# PCI_short_card_universal_-_32_BIT-6.net
KiCad netlist of a schematic drawn in Altium Designer
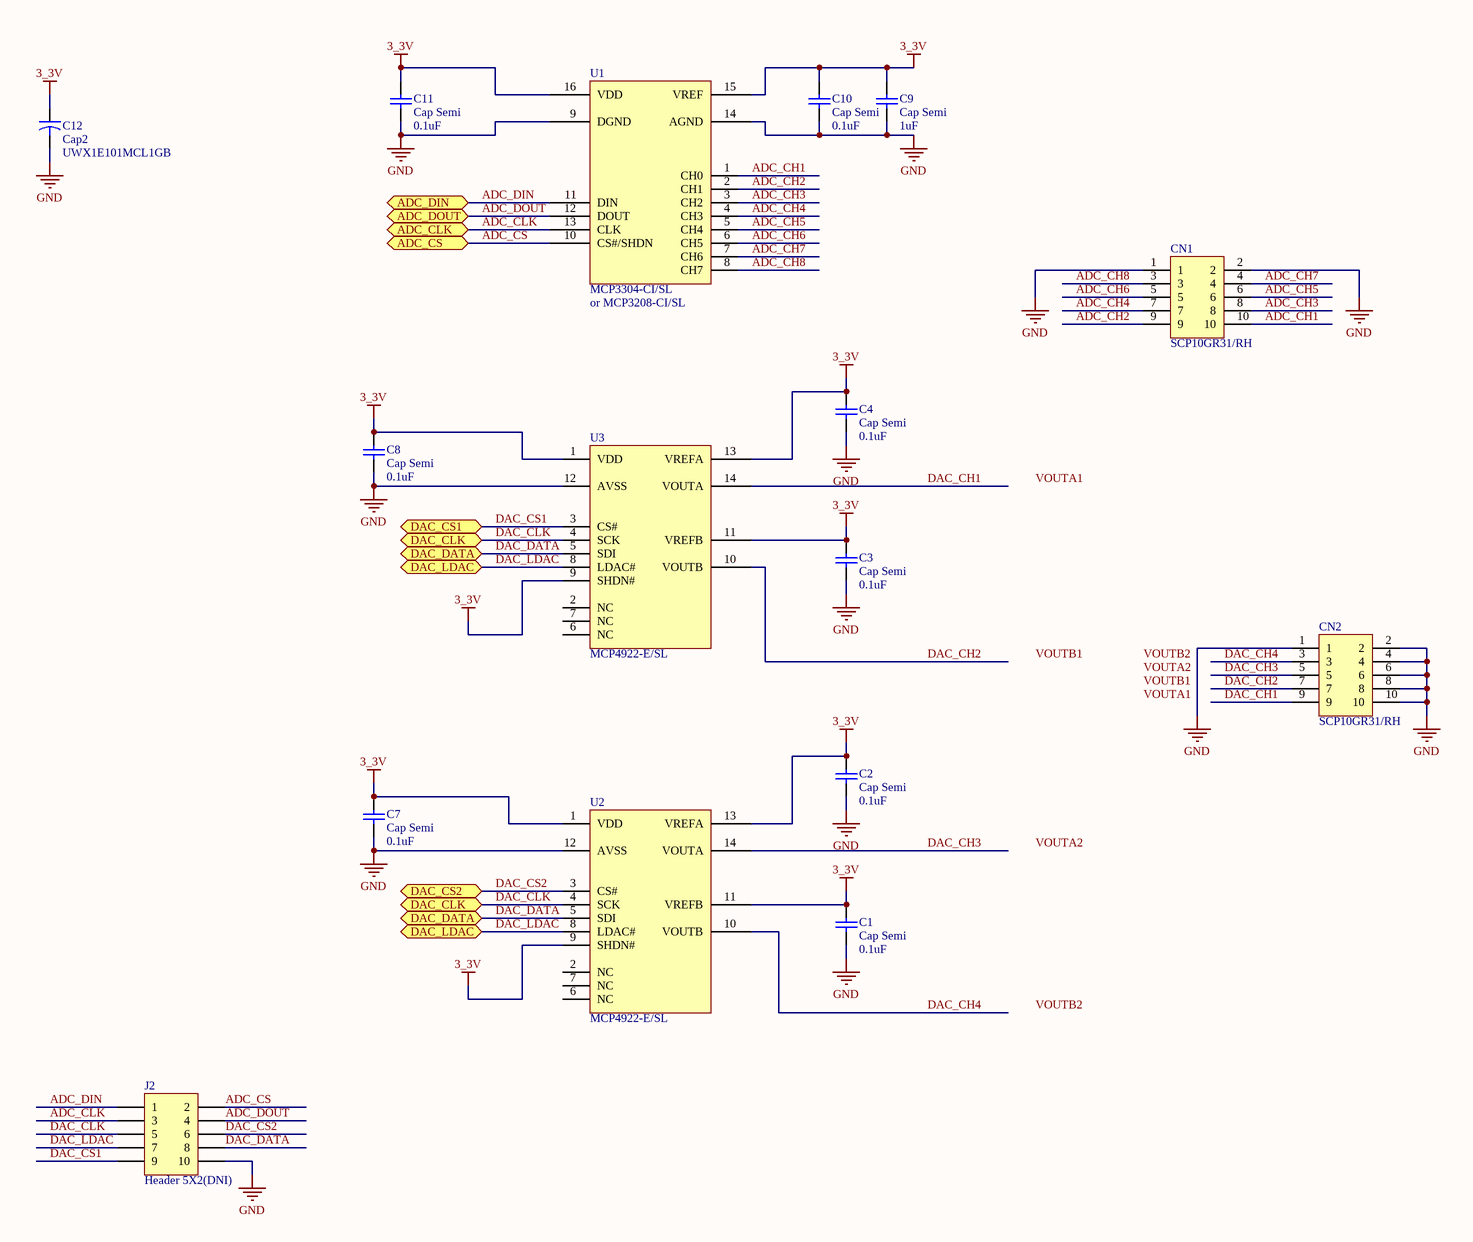
[diagram p0: PCI short card universal - 32 BIT-6.schdoc]

(export (version "E")
  (design (tool "Eeschema 10.0.6"))
  (components
    (comp (ref "C1")
      (value "Cap Semi")
      (footprint "RESC1608N")
      (description "Capacitor (Semiconductor SIM Model)")
      (fields (field (name "ALTIUM_VALUE") "0.1uF") (field (name "PUBLISHER") "Altium Limited"))
      (libsource (lib "Miscellaneous Devices") (part "Cap Semi"))
    )
    (comp (ref "C2")
      (value "Cap Semi")
      (footprint "RESC1608N")
      (description "Capacitor (Semiconductor SIM Model)")
      (fields (field (name "ALTIUM_VALUE") "0.1uF") (field (name "PUBLISHER") "Altium Limited"))
      (libsource (lib "Miscellaneous Devices") (part "Cap Semi"))
    )
    (comp (ref "C3")
      (value "Cap Semi")
      (footprint "RESC1608N")
      (description "Capacitor (Semiconductor SIM Model)")
      (fields (field (name "ALTIUM_VALUE") "0.1uF") (field (name "PUBLISHER") "Altium Limited"))
      (libsource (lib "Miscellaneous Devices") (part "Cap Semi"))
    )
    (comp (ref "C4")
      (value "Cap Semi")
      (footprint "RESC1608N")
      (description "Capacitor (Semiconductor SIM Model)")
      (fields (field (name "ALTIUM_VALUE") "0.1uF") (field (name "PUBLISHER") "Altium Limited"))
      (libsource (lib "Miscellaneous Devices") (part "Cap Semi"))
    )
    (comp (ref "C7")
      (value "Cap Semi")
      (footprint "RESC1608N")
      (description "Capacitor (Semiconductor SIM Model)")
      (fields (field (name "ALTIUM_VALUE") "0.1uF") (field (name "PUBLISHER") "Altium Limited"))
      (libsource (lib "Miscellaneous Devices") (part "Cap Semi"))
    )
    (comp (ref "C8")
      (value "Cap Semi")
      (footprint "RESC1608N")
      (description "Capacitor (Semiconductor SIM Model)")
      (fields (field (name "ALTIUM_VALUE") "0.1uF") (field (name "PUBLISHER") "Altium Limited"))
      (libsource (lib "Miscellaneous Devices") (part "Cap Semi"))
    )
    (comp (ref "C9")
      (value "Cap Semi")
      (footprint "RESC1608N")
      (description "Capacitor (Semiconductor SIM Model)")
      (fields (field (name "ALTIUM_VALUE") "1uF") (field (name "PUBLISHER") "Altium Limited"))
      (libsource (lib "Miscellaneous Devices") (part "Cap Semi"))
    )
    (comp (ref "C10")
      (value "Cap Semi")
      (footprint "RESC1608N")
      (description "Capacitor (Semiconductor SIM Model)")
      (fields (field (name "ALTIUM_VALUE") "0.1uF") (field (name "PUBLISHER") "Altium Limited"))
      (libsource (lib "Miscellaneous Devices") (part "Cap Semi"))
    )
    (comp (ref "C11")
      (value "Cap Semi")
      (footprint "RESC1608N")
      (description "Capacitor (Semiconductor SIM Model)")
      (fields (field (name "ALTIUM_VALUE") "0.1uF") (field (name "PUBLISHER") "Altium Limited"))
      (libsource (lib "Miscellaneous Devices") (part "Cap Semi"))
    )
    (comp (ref "C12")
      (value "Cap2")
      (footprint "ECEL_D8")
      (description "NICHICON")
      (fields (field (name "ALTIUM_VALUE") "UWX1E101MCL1GB") (field (name "PUBLISHER") "Altium Limited"))
      (libsource (lib "Miscellaneous Devices") (part "Cap2"))
    )
    (comp (ref "CN1")
      (value "SCP10GR31/RH")
      (footprint "SCP10GR31/RH")
      (description "GTK")
      (libsource (lib "Schlib1") (part "SCP10GR31/RH"))
    )
    (comp (ref "CN2")
      (value "SCP10GR31/RH")
      (footprint "SCP10GR31/RH")
      (description "GTK")
      (libsource (lib "Schlib1") (part "SCP10GR31/RH"))
    )
    (comp (ref "J2")
      (value "Header 5X2(DNI)")
      (footprint "HDR2X5")
      (description "Header, 5-Pin, Dual row")
      (fields (field (name "PUBLISHER") "Altium Limited"))
      (libsource (lib "Miscellaneous Connectors") (part "Header 5X2"))
    )
    (comp (ref "U1")
      (value "MCP3304-CI/SL")
      (footprint "MCP3304-CI/SL")
      (description "MICROCHIPS")
      (libsource (lib "Schlib1") (part "MCP3304-CI/SL"))
    )
    (comp (ref "U2")
      (value "MCP4922-E/SL")
      (footprint "MCP4922-E/SL")
      (description "MICROCHIPS")
      (libsource (lib "Schlib1") (part "MCP4922-E/SL"))
    )
    (comp (ref "U3")
      (value "MCP4922-E/SL")
      (footprint "MCP4922-E/SL")
      (description "MICROCHIPS")
      (libsource (lib "Schlib1") (part "MCP4922-E/SL"))
    )
  )
  (nets
    (net (code "1") (name "/ADC_CH1") (class "Default")
      (node (ref "CN1") (pin "10") (pinfunction "10_10") (pintype "passive"))
      (node (ref "U1") (pin "1") (pinfunction "CH0_1") (pintype "passive"))
    )
    (net (code "2") (name "/ADC_CH2") (class "Default")
      (node (ref "CN1") (pin "9") (pinfunction "9_9") (pintype "passive"))
      (node (ref "U1") (pin "2") (pinfunction "CH1_2") (pintype "passive"))
    )
    (net (code "3") (name "/ADC_CH3") (class "Default")
      (node (ref "CN1") (pin "8") (pinfunction "8_8") (pintype "passive"))
      (node (ref "U1") (pin "3") (pinfunction "CH2_3") (pintype "passive"))
    )
    (net (code "4") (name "/ADC_CH4") (class "Default")
      (node (ref "CN1") (pin "7") (pinfunction "7_7") (pintype "passive"))
      (node (ref "U1") (pin "4") (pinfunction "CH3_4") (pintype "passive"))
    )
    (net (code "5") (name "/ADC_CH5") (class "Default")
      (node (ref "CN1") (pin "6") (pinfunction "6_6") (pintype "passive"))
      (node (ref "U1") (pin "5") (pinfunction "CH4_5") (pintype "passive"))
    )
    (net (code "6") (name "/ADC_CH6") (class "Default")
      (node (ref "CN1") (pin "5") (pinfunction "5_5") (pintype "passive"))
      (node (ref "U1") (pin "6") (pinfunction "CH5_6") (pintype "passive"))
    )
    (net (code "7") (name "/ADC_CH7") (class "Default")
      (node (ref "CN1") (pin "4") (pinfunction "4_4") (pintype "passive"))
      (node (ref "U1") (pin "7") (pinfunction "CH6_7") (pintype "passive"))
    )
    (net (code "8") (name "/ADC_CH8") (class "Default")
      (node (ref "CN1") (pin "3") (pinfunction "3_3") (pintype "passive"))
      (node (ref "U1") (pin "8") (pinfunction "CH7_8") (pintype "passive"))
    )
    (net (code "9") (name "/ADC_CLK") (class "Default")
      (node (ref "J2") (pin "3") (pinfunction "3_3") (pintype "passive"))
      (node (ref "U1") (pin "13") (pinfunction "CLK_13") (pintype "passive"))
    )
    (net (code "10") (name "/ADC_CS") (class "Default")
      (node (ref "J2") (pin "2") (pinfunction "2_2") (pintype "passive"))
      (node (ref "U1") (pin "10") (pinfunction "CS#/SHDN_10") (pintype "passive"))
    )
    (net (code "11") (name "/ADC_DIN") (class "Default")
      (node (ref "J2") (pin "1") (pinfunction "1_1") (pintype "passive"))
      (node (ref "U1") (pin "11") (pinfunction "DIN_11") (pintype "passive"))
    )
    (net (code "12") (name "/ADC_DOUT") (class "Default")
      (node (ref "J2") (pin "4") (pinfunction "4_4") (pintype "passive"))
      (node (ref "U1") (pin "12") (pinfunction "DOUT_12") (pintype "passive"))
    )
    (net (code "13") (name "/DAC_CH1") (class "Default")
      (node (ref "CN2") (pin "9") (pinfunction "9_9") (pintype "passive"))
      (node (ref "U3") (pin "14") (pinfunction "VOUTA_14") (pintype "passive"))
    )
    (net (code "14") (name "/DAC_CH2") (class "Default")
      (node (ref "CN2") (pin "7") (pinfunction "7_7") (pintype "passive"))
      (node (ref "U3") (pin "10") (pinfunction "VOUTB_10") (pintype "passive"))
    )
    (net (code "15") (name "/DAC_CH3") (class "Default")
      (node (ref "CN2") (pin "5") (pinfunction "5_5") (pintype "passive"))
      (node (ref "U2") (pin "14") (pinfunction "VOUTA_14") (pintype "passive"))
    )
    (net (code "16") (name "/DAC_CH4") (class "Default")
      (node (ref "CN2") (pin "3") (pinfunction "3_3") (pintype "passive"))
      (node (ref "U2") (pin "10") (pinfunction "VOUTB_10") (pintype "passive"))
    )
    (net (code "17") (name "/DAC_CLK") (class "Default")
      (node (ref "J2") (pin "5") (pinfunction "5_5") (pintype "passive"))
      (node (ref "U2") (pin "4") (pinfunction "SCK_4") (pintype "passive"))
      (node (ref "U3") (pin "4") (pinfunction "SCK_4") (pintype "passive"))
    )
    (net (code "18") (name "/DAC_CS1") (class "Default")
      (node (ref "J2") (pin "9") (pinfunction "9_9") (pintype "passive"))
      (node (ref "U3") (pin "3") (pinfunction "CS#_3") (pintype "passive"))
    )
    (net (code "19") (name "/DAC_CS2") (class "Default")
      (node (ref "J2") (pin "6") (pinfunction "6_6") (pintype "passive"))
      (node (ref "U2") (pin "3") (pinfunction "CS#_3") (pintype "passive"))
    )
    (net (code "20") (name "/DAC_DATA") (class "Default")
      (node (ref "J2") (pin "8") (pinfunction "8_8") (pintype "passive"))
      (node (ref "U2") (pin "5") (pinfunction "SDI_5") (pintype "passive"))
      (node (ref "U3") (pin "5") (pinfunction "SDI_5") (pintype "passive"))
    )
    (net (code "21") (name "/DAC_LDAC") (class "Default")
      (node (ref "J2") (pin "7") (pinfunction "7_7") (pintype "passive"))
      (node (ref "U2") (pin "8") (pinfunction "LDAC#_8") (pintype "passive"))
      (node (ref "U3") (pin "8") (pinfunction "LDAC#_8") (pintype "passive"))
    )
    (net (code "26") (name "3_3V") (class "Default")
      (node (ref "C1") (pin "2") (pinfunction "2_2") (pintype "passive"))
      (node (ref "C10") (pin "2") (pinfunction "2_2") (pintype "passive"))
      (node (ref "C11") (pin "2") (pinfunction "2_2") (pintype "passive"))
      (node (ref "C12") (pin "1") (pinfunction "1_1") (pintype "passive"))
      (node (ref "C2") (pin "2") (pinfunction "2_2") (pintype "passive"))
      (node (ref "C3") (pin "2") (pinfunction "2_2") (pintype "passive"))
      (node (ref "C4") (pin "2") (pinfunction "2_2") (pintype "passive"))
      (node (ref "C7") (pin "2") (pinfunction "2_2") (pintype "passive"))
      (node (ref "C8") (pin "2") (pinfunction "2_2") (pintype "passive"))
      (node (ref "C9") (pin "2") (pinfunction "2_2") (pintype "passive"))
      (node (ref "U1") (pin "15") (pinfunction "VREF_15") (pintype "passive"))
      (node (ref "U1") (pin "16") (pinfunction "VDD_16") (pintype "passive"))
      (node (ref "U2") (pin "1") (pinfunction "VDD_1") (pintype "passive"))
      (node (ref "U2") (pin "11") (pinfunction "VREFB_11") (pintype "passive"))
      (node (ref "U2") (pin "13") (pinfunction "VREFA_13") (pintype "passive"))
      (node (ref "U2") (pin "9") (pinfunction "SHDN#_9") (pintype "passive"))
      (node (ref "U3") (pin "1") (pinfunction "VDD_1") (pintype "passive"))
      (node (ref "U3") (pin "11") (pinfunction "VREFB_11") (pintype "passive"))
      (node (ref "U3") (pin "13") (pinfunction "VREFA_13") (pintype "passive"))
      (node (ref "U3") (pin "9") (pinfunction "SHDN#_9") (pintype "passive"))
    )
    (net (code "27") (name "GND") (class "Default")
      (node (ref "C1") (pin "1") (pinfunction "1_1") (pintype "passive"))
      (node (ref "C10") (pin "1") (pinfunction "1_1") (pintype "passive"))
      (node (ref "C11") (pin "1") (pinfunction "1_1") (pintype "passive"))
      (node (ref "C12") (pin "2") (pinfunction "2_2") (pintype "passive"))
      (node (ref "C2") (pin "1") (pinfunction "1_1") (pintype "passive"))
      (node (ref "C3") (pin "1") (pinfunction "1_1") (pintype "passive"))
      (node (ref "C4") (pin "1") (pinfunction "1_1") (pintype "passive"))
      (node (ref "C7") (pin "1") (pinfunction "1_1") (pintype "passive"))
      (node (ref "C8") (pin "1") (pinfunction "1_1") (pintype "passive"))
      (node (ref "C9") (pin "1") (pinfunction "1_1") (pintype "passive"))
      (node (ref "CN1") (pin "1") (pinfunction "1_1") (pintype "passive"))
      (node (ref "CN1") (pin "2") (pinfunction "2_2") (pintype "passive"))
      (node (ref "CN2") (pin "1") (pinfunction "1_1") (pintype "passive"))
      (node (ref "CN2") (pin "10") (pinfunction "10_10") (pintype "passive"))
      (node (ref "CN2") (pin "2") (pinfunction "2_2") (pintype "passive"))
      (node (ref "CN2") (pin "4") (pinfunction "4_4") (pintype "passive"))
      (node (ref "CN2") (pin "6") (pinfunction "6_6") (pintype "passive"))
      (node (ref "CN2") (pin "8") (pinfunction "8_8") (pintype "passive"))
      (node (ref "J2") (pin "10") (pinfunction "10_10") (pintype "passive"))
      (node (ref "U1") (pin "14") (pinfunction "AGND_14") (pintype "passive"))
      (node (ref "U1") (pin "9") (pinfunction "DGND_9") (pintype "passive"))
      (node (ref "U2") (pin "12") (pinfunction "AVSS_12") (pintype "passive"))
      (node (ref "U3") (pin "12") (pinfunction "AVSS_12") (pintype "passive"))
    )
    (net (code "28") (name "unconnected-(U2-NC-Pad2)") (class "Default")
      (node (ref "U2") (pin "2") (pinfunction "NC_2") (pintype "passive"))
    )
    (net (code "29") (name "unconnected-(U2-NC-Pad6)") (class "Default")
      (node (ref "U2") (pin "6") (pinfunction "NC_6") (pintype "passive"))
    )
    (net (code "30") (name "unconnected-(U2-NC-Pad7)") (class "Default")
      (node (ref "U2") (pin "7") (pinfunction "NC_7") (pintype "passive"))
    )
    (net (code "31") (name "unconnected-(U3-NC-Pad2)") (class "Default")
      (node (ref "U3") (pin "2") (pinfunction "NC_2") (pintype "passive"))
    )
    (net (code "32") (name "unconnected-(U3-NC-Pad6)") (class "Default")
      (node (ref "U3") (pin "6") (pinfunction "NC_6") (pintype "passive"))
    )
    (net (code "33") (name "unconnected-(U3-NC-Pad7)") (class "Default")
      (node (ref "U3") (pin "7") (pinfunction "NC_7") (pintype "passive"))
    )
  )
)
